# antenna_array.net
KiCad netlist of a schematic drawn in Altium Designer
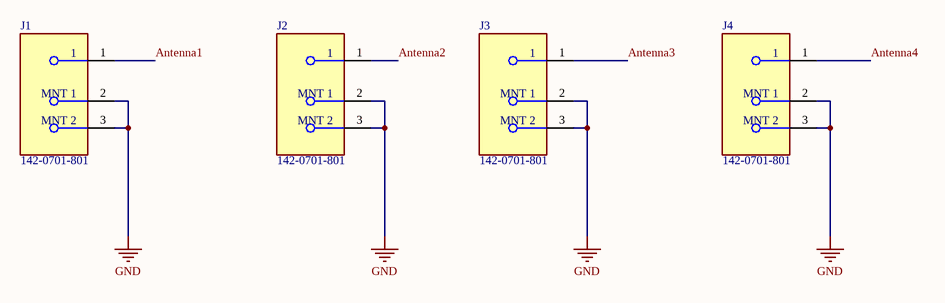
[diagram p0: antenna_array.SchDoc]

(export (version "E")
  (design (tool "Eeschema 10.0.6"))
  (components
    (comp (ref "J1")
      (value "142-0701-801")
      (footprint "FP-142-0701-801-MFG")
      (description "CONN SMA JACK STR 50OHM EDGE MNT")
      (libsource (lib "Altium Content Vault") (part "89929399afe843c8b6880c6cbd0f99a"))
    )
    (comp (ref "J2")
      (value "142-0701-801")
      (footprint "FP-142-0701-801-MFG")
      (description "CONN SMA JACK STR 50OHM EDGE MNT")
      (libsource (lib "Altium Content Vault") (part "89929399afe843c8b6880c6cbd0f99a"))
    )
    (comp (ref "J3")
      (value "142-0701-801")
      (footprint "FP-142-0701-801-MFG")
      (description "CONN SMA JACK STR 50OHM EDGE MNT")
      (libsource (lib "Altium Content Vault") (part "89929399afe843c8b6880c6cbd0f99a"))
    )
    (comp (ref "J4")
      (value "142-0701-801")
      (footprint "FP-142-0701-801-MFG")
      (description "CONN SMA JACK STR 50OHM EDGE MNT")
      (libsource (lib "Altium Content Vault") (part "89929399afe843c8b6880c6cbd0f99a"))
    )
  )
  (nets
    (net (code "1") (name "/Antenna1") (class "Default")
      (node (ref "J1") (pin "1") (pinfunction "1_1") (pintype "passive"))
    )
    (net (code "2") (name "/Antenna2") (class "Default")
      (node (ref "J2") (pin "1") (pinfunction "1_1") (pintype "passive"))
    )
    (net (code "3") (name "/Antenna3") (class "Default")
      (node (ref "J3") (pin "1") (pinfunction "1_1") (pintype "passive"))
    )
    (net (code "4") (name "/Antenna4") (class "Default")
      (node (ref "J4") (pin "1") (pinfunction "1_1") (pintype "passive"))
    )
    (net (code "5") (name "GND") (class "Default")
      (node (ref "J1") (pin "2") (pinfunction "MNT_1_2") (pintype "passive"))
      (node (ref "J1") (pin "3") (pinfunction "MNT_2_3") (pintype "passive"))
      (node (ref "J2") (pin "2") (pinfunction "MNT_1_2") (pintype "passive"))
      (node (ref "J2") (pin "3") (pinfunction "MNT_2_3") (pintype "passive"))
      (node (ref "J3") (pin "2") (pinfunction "MNT_1_2") (pintype "passive"))
      (node (ref "J3") (pin "3") (pinfunction "MNT_2_3") (pintype "passive"))
      (node (ref "J4") (pin "2") (pinfunction "MNT_1_2") (pintype "passive"))
      (node (ref "J4") (pin "3") (pinfunction "MNT_2_3") (pintype "passive"))
    )
  )
)
